# 01.net
KiCad netlist of a schematic drawn in EAGLE
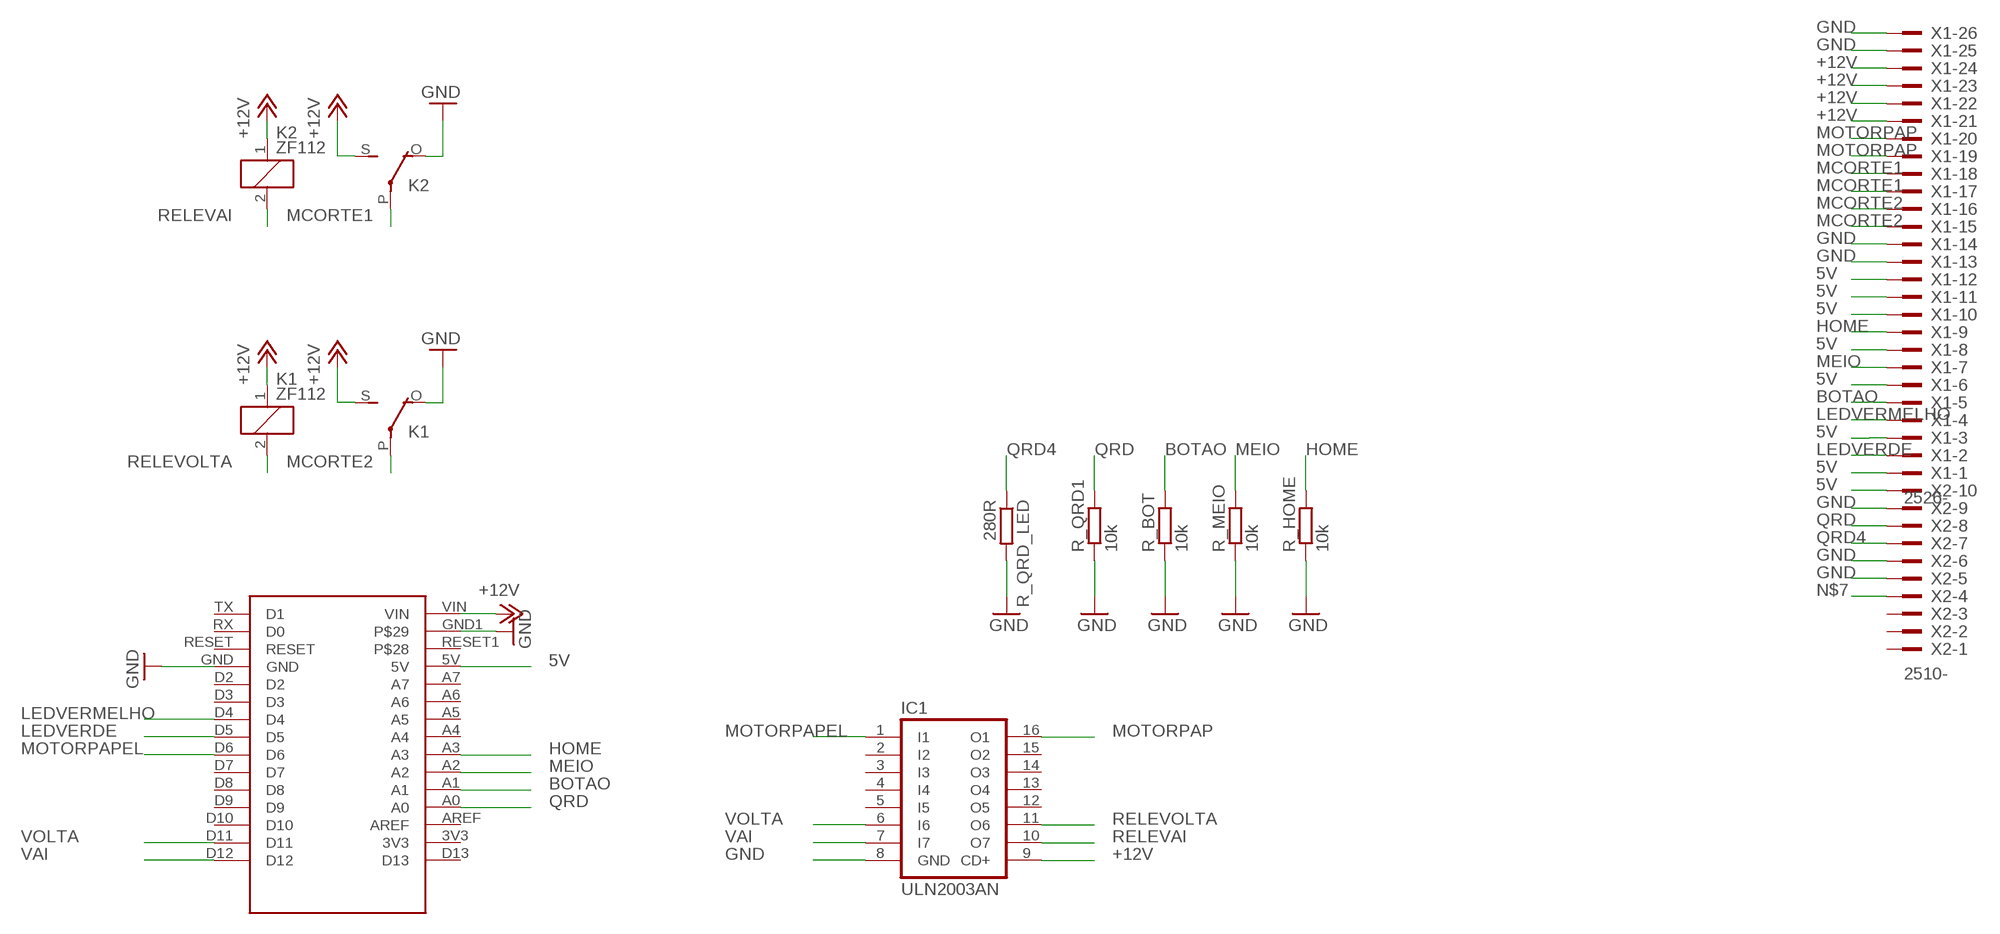
[diagram p0: schematic, sheet 1]

(export (version "E")
  (design (tool "Eeschema 10.0.6"))
  (components
    (comp (ref "IC1")
      (value "ULN2003AN")
      (footprint "eagle-import:DIL16")
      (libsource (lib "eagle-import") (part "ULN2003AN"))
    )
    (comp (ref "K1")
      (value "ZF112")
      (footprint "eagle-import:ZF112")
      (libsource (lib "eagle-import") (part "ZF112"))
    )
    (comp (ref "K2")
      (value "ZF112")
      (footprint "eagle-import:ZF112")
      (fields (field (name "OC_FARNELL") "unknown") (field (name "OC_NEWARK") "unknown"))
      (libsource (lib "eagle-import") (part "ZF112"))
    )
    (comp (ref "R_BOT")
      (value "10k")
      (footprint "eagle-import:0207_15")
      (libsource (lib "eagle-import") (part "R-EU_0207/15"))
    )
    (comp (ref "R_HOME")
      (value "10k")
      (footprint "eagle-import:0207_15")
      (libsource (lib "eagle-import") (part "R-EU_0207/15"))
    )
    (comp (ref "R_MEIO")
      (value "10k")
      (footprint "eagle-import:0207_15")
      (libsource (lib "eagle-import") (part "R-EU_0207/15"))
    )
    (comp (ref "R_QRD1")
      (value "10k")
      (footprint "eagle-import:0207_15")
      (libsource (lib "eagle-import") (part "R-EU_0207/15"))
    )
    (comp (ref "R_QRD_LED")
      (value "280R")
      (footprint "eagle-import:0204_7")
      (libsource (lib "eagle-import") (part "R-EU_0204/7"))
    )
    (comp (ref "U$1")
      (value "ARDUINONANO")
      (footprint "eagle-import:NANO")
      (libsource (lib "eagle-import") (part "ARDUINONANO"))
    )
    (comp (ref "X1")
      (value "2526-")
      (footprint "eagle-import:PAK100_2500-26")
      (libsource (lib "eagle-import") (part "2526-"))
    )
    (comp (ref "X2")
      (value "2510-")
      (footprint "eagle-import:PAK100_2500-10")
      (fields (field (name "MF") "3M") (field (name "MPN") "2510-6002UB"))
      (libsource (lib "eagle-import") (part "2510-"))
    )
  )
  (nets
    (net (code "1") (name "+12V") (class "Default")
      (node (ref "IC1") (pin "9") (pinfunction "CD+_9") (pintype "passive"))
      (node (ref "K1") (pin "1") (pinfunction "1_1") (pintype "passive"))
      (node (ref "K1") (pin "S") (pinfunction "S_S") (pintype "passive"))
      (node (ref "K2") (pin "1") (pinfunction "1_1") (pintype "passive"))
      (node (ref "K2") (pin "S") (pinfunction "S_S") (pintype "passive"))
      (node (ref "U$1") (pin "VIN") (pinfunction "VIN_VIN") (pintype "bidirectional"))
      (node (ref "X1") (pin "21") (pinfunction "KL_21") (pintype "passive"))
      (node (ref "X1") (pin "22") (pinfunction "KL_22") (pintype "passive"))
      (node (ref "X1") (pin "23") (pinfunction "KL_23") (pintype "passive"))
      (node (ref "X1") (pin "24") (pinfunction "KL_24") (pintype "passive"))
    )
    (net (code "2") (name "/5V") (class "Default")
      (node (ref "U$1") (pin "5V") (pinfunction "5V_5V") (pintype "bidirectional"))
      (node (ref "X1") (pin "1") (pinfunction "KL_1") (pintype "passive"))
      (node (ref "X1") (pin "10") (pinfunction "KL_10") (pintype "passive"))
      (node (ref "X1") (pin "11") (pinfunction "KL_11") (pintype "passive"))
      (node (ref "X1") (pin "12") (pinfunction "KL_12") (pintype "passive"))
      (node (ref "X1") (pin "3") (pinfunction "KL_3") (pintype "passive"))
      (node (ref "X1") (pin "6") (pinfunction "KL_6") (pintype "passive"))
      (node (ref "X1") (pin "8") (pinfunction "KL_8") (pintype "passive"))
      (node (ref "X2") (pin "10") (pinfunction "KL_10") (pintype "passive"))
    )
    (net (code "3") (name "/BOTAO") (class "Default")
      (node (ref "R_BOT") (pin "2") (pinfunction "2_2") (pintype "passive"))
      (node (ref "U$1") (pin "A1") (pinfunction "A1_A1") (pintype "bidirectional"))
      (node (ref "X1") (pin "5") (pinfunction "KL_5") (pintype "passive"))
    )
    (net (code "4") (name "/HOME") (class "Default")
      (node (ref "R_HOME") (pin "2") (pinfunction "2_2") (pintype "passive"))
      (node (ref "U$1") (pin "A3") (pinfunction "A3_A3") (pintype "bidirectional"))
      (node (ref "X1") (pin "9") (pinfunction "KL_9") (pintype "passive"))
    )
    (net (code "5") (name "/LEDVERDE") (class "Default")
      (node (ref "U$1") (pin "D5") (pinfunction "D5_D5") (pintype "bidirectional"))
      (node (ref "X1") (pin "2") (pinfunction "KL_2") (pintype "passive"))
    )
    (net (code "6") (name "/LEDVERMELHO") (class "Default")
      (node (ref "U$1") (pin "D4") (pinfunction "D4_D4") (pintype "bidirectional"))
      (node (ref "X1") (pin "4") (pinfunction "KL_4") (pintype "passive"))
    )
    (net (code "7") (name "/MCORTE1") (class "Default")
      (node (ref "K2") (pin "P") (pinfunction "P_P") (pintype "passive"))
      (node (ref "X1") (pin "17") (pinfunction "KL_17") (pintype "passive"))
      (node (ref "X1") (pin "18") (pinfunction "KL_18") (pintype "passive"))
    )
    (net (code "8") (name "/MCORTE2") (class "Default")
      (node (ref "K1") (pin "P") (pinfunction "P_P") (pintype "passive"))
      (node (ref "X1") (pin "15") (pinfunction "KL_15") (pintype "passive"))
      (node (ref "X1") (pin "16") (pinfunction "KL_16") (pintype "passive"))
    )
    (net (code "9") (name "/MEIO") (class "Default")
      (node (ref "R_MEIO") (pin "2") (pinfunction "2_2") (pintype "passive"))
      (node (ref "U$1") (pin "A2") (pinfunction "A2_A2") (pintype "bidirectional"))
      (node (ref "X1") (pin "7") (pinfunction "KL_7") (pintype "passive"))
    )
    (net (code "10") (name "/MOTORPAP") (class "Default")
      (node (ref "IC1") (pin "16") (pinfunction "O1_16") (pintype "open_collector"))
      (node (ref "X1") (pin "19") (pinfunction "KL_19") (pintype "passive"))
      (node (ref "X1") (pin "20") (pinfunction "KL_20") (pintype "passive"))
    )
    (net (code "11") (name "/MOTORPAPEL") (class "Default")
      (node (ref "IC1") (pin "1") (pinfunction "I1_1") (pintype "input"))
      (node (ref "U$1") (pin "D6") (pinfunction "D6_D6") (pintype "bidirectional"))
    )
    (net (code "12") (name "/N$7") (class "Default")
      (node (ref "X2") (pin "4") (pinfunction "KL_4") (pintype "passive"))
    )
    (net (code "13") (name "/QRD") (class "Default")
      (node (ref "R_QRD1") (pin "2") (pinfunction "2_2") (pintype "passive"))
      (node (ref "U$1") (pin "A0") (pinfunction "A0_A0") (pintype "bidirectional"))
      (node (ref "X2") (pin "8") (pinfunction "KL_8") (pintype "passive"))
    )
    (net (code "14") (name "/QRD4") (class "Default")
      (node (ref "R_QRD_LED") (pin "1") (pinfunction "1_1") (pintype "passive"))
      (node (ref "X2") (pin "7") (pinfunction "KL_7") (pintype "passive"))
    )
    (net (code "15") (name "/RELEVAI") (class "Default")
      (node (ref "IC1") (pin "10") (pinfunction "O7_10") (pintype "open_collector"))
      (node (ref "K2") (pin "2") (pinfunction "2_2") (pintype "passive"))
    )
    (net (code "16") (name "/RELEVOLTA") (class "Default")
      (node (ref "IC1") (pin "11") (pinfunction "O6_11") (pintype "open_collector"))
      (node (ref "K1") (pin "2") (pinfunction "2_2") (pintype "passive"))
    )
    (net (code "17") (name "/VAI") (class "Default")
      (node (ref "IC1") (pin "7") (pinfunction "I7_7") (pintype "input"))
      (node (ref "U$1") (pin "D12") (pinfunction "D12_D12") (pintype "bidirectional"))
    )
    (net (code "18") (name "/VOLTA") (class "Default")
      (node (ref "IC1") (pin "6") (pinfunction "I6_6") (pintype "input"))
      (node (ref "U$1") (pin "D11") (pinfunction "D11_D11") (pintype "bidirectional"))
    )
    (net (code "19") (name "GND") (class "Default")
      (node (ref "IC1") (pin "8") (pinfunction "GND_8") (pintype "power_in"))
      (node (ref "K1") (pin "O") (pinfunction "O_O") (pintype "passive"))
      (node (ref "K2") (pin "O") (pinfunction "O_O") (pintype "passive"))
      (node (ref "R_BOT") (pin "1") (pinfunction "1_1") (pintype "passive"))
      (node (ref "R_HOME") (pin "1") (pinfunction "1_1") (pintype "passive"))
      (node (ref "R_MEIO") (pin "1") (pinfunction "1_1") (pintype "passive"))
      (node (ref "R_QRD1") (pin "1") (pinfunction "1_1") (pintype "passive"))
      (node (ref "R_QRD_LED") (pin "2") (pinfunction "2_2") (pintype "passive"))
      (node (ref "U$1") (pin "GND") (pinfunction "GND_GND") (pintype "bidirectional"))
      (node (ref "U$1") (pin "GND1") (pinfunction "P$29_GND1") (pintype "bidirectional"))
      (node (ref "X1") (pin "13") (pinfunction "KL_13") (pintype "passive"))
      (node (ref "X1") (pin "14") (pinfunction "KL_14") (pintype "passive"))
      (node (ref "X1") (pin "25") (pinfunction "KL_25") (pintype "passive"))
      (node (ref "X1") (pin "26") (pinfunction "KL_26") (pintype "passive"))
      (node (ref "X2") (pin "5") (pinfunction "KL_5") (pintype "passive"))
      (node (ref "X2") (pin "6") (pinfunction "KL_6") (pintype "passive"))
      (node (ref "X2") (pin "9") (pinfunction "KL_9") (pintype "passive"))
    )
    (net (code "20") (name "unconnected-(IC1-I2-Pad2)") (class "Default")
      (node (ref "IC1") (pin "2") (pinfunction "I2_2") (pintype "input"))
    )
    (net (code "21") (name "unconnected-(IC1-I3-Pad3)") (class "Default")
      (node (ref "IC1") (pin "3") (pinfunction "I3_3") (pintype "input"))
    )
    (net (code "22") (name "unconnected-(IC1-I4-Pad4)") (class "Default")
      (node (ref "IC1") (pin "4") (pinfunction "I4_4") (pintype "input"))
    )
    (net (code "23") (name "unconnected-(IC1-I5-Pad5)") (class "Default")
      (node (ref "IC1") (pin "5") (pinfunction "I5_5") (pintype "input"))
    )
    (net (code "24") (name "unconnected-(IC1-O2-Pad15)") (class "Default")
      (node (ref "IC1") (pin "15") (pinfunction "O2_15") (pintype "open_collector"))
    )
    (net (code "25") (name "unconnected-(IC1-O3-Pad14)") (class "Default")
      (node (ref "IC1") (pin "14") (pinfunction "O3_14") (pintype "open_collector"))
    )
    (net (code "26") (name "unconnected-(IC1-O4-Pad13)") (class "Default")
      (node (ref "IC1") (pin "13") (pinfunction "O4_13") (pintype "open_collector"))
    )
    (net (code "27") (name "unconnected-(IC1-O5-Pad12)") (class "Default")
      (node (ref "IC1") (pin "12") (pinfunction "O5_12") (pintype "open_collector"))
    )
    (net (code "28") (name "unconnected-(U$1-D0-PadRX)") (class "Default")
      (node (ref "U$1") (pin "RX") (pinfunction "D0_RX") (pintype "bidirectional"))
    )
    (net (code "29") (name "unconnected-(U$1-D1-PadTX)") (class "Default")
      (node (ref "U$1") (pin "TX") (pinfunction "D1_TX") (pintype "bidirectional"))
    )
    (net (code "30") (name "unconnected-(U$1-P$28-PadRESET1)") (class "Default")
      (node (ref "U$1") (pin "RESET1") (pinfunction "P$28_RESET1") (pintype "bidirectional"))
    )
    (net (code "31") (name "unconnected-(U$1-Pad3V3)") (class "Default")
      (node (ref "U$1") (pin "3V3") (pinfunction "3V3_3V3") (pintype "bidirectional"))
    )
    (net (code "32") (name "unconnected-(U$1-PadA4)") (class "Default")
      (node (ref "U$1") (pin "A4") (pinfunction "A4_A4") (pintype "bidirectional"))
    )
    (net (code "33") (name "unconnected-(U$1-PadA5)") (class "Default")
      (node (ref "U$1") (pin "A5") (pinfunction "A5_A5") (pintype "bidirectional"))
    )
    (net (code "34") (name "unconnected-(U$1-PadA6)") (class "Default")
      (node (ref "U$1") (pin "A6") (pinfunction "A6_A6") (pintype "bidirectional"))
    )
    (net (code "35") (name "unconnected-(U$1-PadA7)") (class "Default")
      (node (ref "U$1") (pin "A7") (pinfunction "A7_A7") (pintype "bidirectional"))
    )
    (net (code "36") (name "unconnected-(U$1-PadAREF)") (class "Default")
      (node (ref "U$1") (pin "AREF") (pinfunction "AREF_AREF") (pintype "bidirectional"))
    )
    (net (code "37") (name "unconnected-(U$1-PadD2)") (class "Default")
      (node (ref "U$1") (pin "D2") (pinfunction "D2_D2") (pintype "bidirectional"))
    )
    (net (code "38") (name "unconnected-(U$1-PadD3)") (class "Default")
      (node (ref "U$1") (pin "D3") (pinfunction "D3_D3") (pintype "bidirectional"))
    )
    (net (code "39") (name "unconnected-(U$1-PadD7)") (class "Default")
      (node (ref "U$1") (pin "D7") (pinfunction "D7_D7") (pintype "bidirectional"))
    )
    (net (code "40") (name "unconnected-(U$1-PadD8)") (class "Default")
      (node (ref "U$1") (pin "D8") (pinfunction "D8_D8") (pintype "bidirectional"))
    )
    (net (code "41") (name "unconnected-(U$1-PadD9)") (class "Default")
      (node (ref "U$1") (pin "D9") (pinfunction "D9_D9") (pintype "bidirectional"))
    )
    (net (code "42") (name "unconnected-(U$1-PadD10)") (class "Default")
      (node (ref "U$1") (pin "D10") (pinfunction "D10_D10") (pintype "bidirectional"))
    )
    (net (code "43") (name "unconnected-(U$1-PadD13)") (class "Default")
      (node (ref "U$1") (pin "D13") (pinfunction "D13_D13") (pintype "bidirectional"))
    )
    (net (code "44") (name "unconnected-(U$1-PadRESET)") (class "Default")
      (node (ref "U$1") (pin "RESET") (pinfunction "RESET_RESET") (pintype "bidirectional"))
    )
    (net (code "45") (name "unconnected-(X2A-KL-Pad1)") (class "Default")
      (node (ref "X2") (pin "1") (pinfunction "KL_1") (pintype "passive"))
    )
    (net (code "46") (name "unconnected-(X2C-KL-Pad2)") (class "Default")
      (node (ref "X2") (pin "2") (pinfunction "KL_2") (pintype "passive"))
    )
    (net (code "47") (name "unconnected-(X2D-KL-Pad3)") (class "Default")
      (node (ref "X2") (pin "3") (pinfunction "KL_3") (pintype "passive"))
    )
  )
)
